# devices.net
KiCad netlist of a schematic drawn in Altium Designer
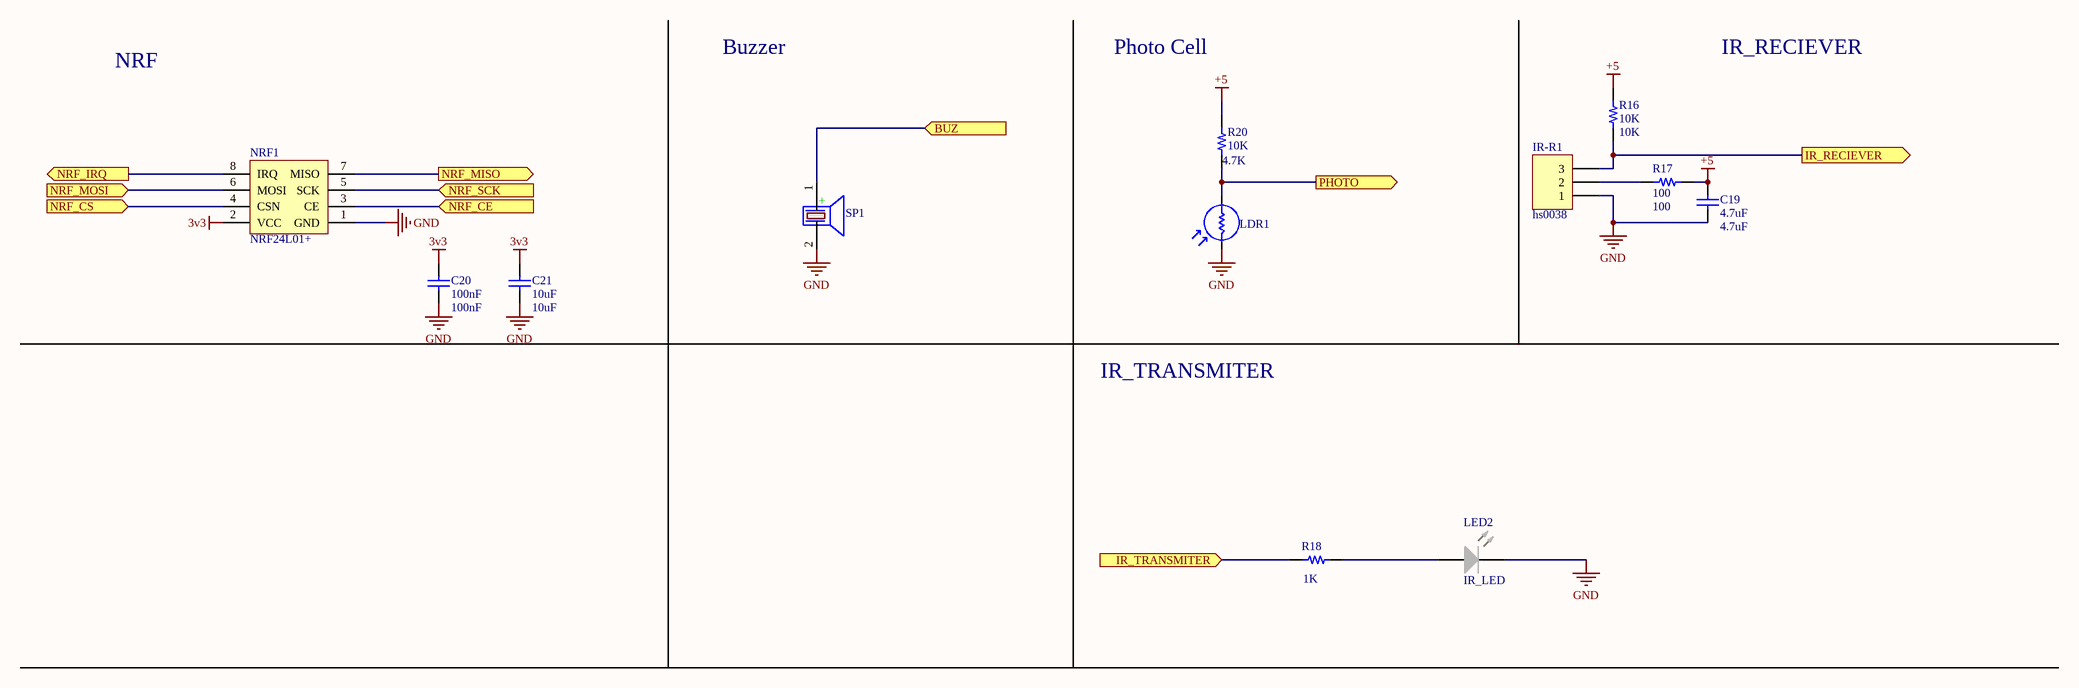
[diagram p0: devices.SchDoc]

(export (version "E")
  (design (tool "Eeschema 10.0.6"))
  (components
    (comp (ref "C19")
      (value "4.7uF")
      (footprint "0603C")
      (description "CAP SMD 0603")
      (fields (field (name "ALTIUM_VALUE") "4.7uF") (field (name "PUBLISHER") "Altium Limited"))
      (libsource (lib "Miscellaneous Devices") (part "Cap"))
    )
    (comp (ref "C20")
      (value "100nF")
      (footprint "0603C")
      (description "CAP SMD 0603")
      (fields (field (name "ALTIUM_VALUE") "100nF") (field (name "PUBLISHER") "Altium Limited"))
      (libsource (lib "Miscellaneous Devices") (part "Cap"))
    )
    (comp (ref "C21")
      (value "10uF")
      (footprint "0603C")
      (description "CAP SMD 0603")
      (fields (field (name "ALTIUM_VALUE") "10uF") (field (name "PUBLISHER") "Altium Limited"))
      (libsource (lib "Miscellaneous Devices") (part "Cap"))
    )
    (comp (ref "IR-R1")
      (value "hs0038")
      (footprint "HS3800B")
      (description "Header, 3-Pin, Right Angle")
      (fields (field (name "PUBLISHER") "Altium Limited"))
      (libsource (lib "Miscellaneous Connectors") (part "Header 3H"))
    )
    (comp (ref "LDR1")
      (value "PhotoCell-5mm")
      (footprint "PhotoCell")
      (description "Photo Cell- Variable Resistor With Light")
      (fields (field (name "DESIGNER") "Saeid Jorablo"))
      (libsource (lib "monitor_panel") (part "LDR"))
    )
    (comp (ref "LED2") (value "IR_LED") (footprint "LED_WHITE") (libsource (lib "LED5") (part "LED-W")))
    (comp (ref "NRF1")
      (value "NRF24L01+")
      (footprint "NRF24L01P")
      (description "NRF Module")
      (libsource (lib "monitor_panel") (part "NRF24L01P"))
    )
    (comp (ref "R16")
      (value "10K")
      (footprint "0603R")
      (description "RES SMD 0603")
      (fields (field (name "PART NUMBER") "RCS0805100KFKEA") (field (name "ALTIUM_VALUE") "10K"))
      (libsource (lib "lamp control-ver2") (part "Resistor"))
    )
    (comp (ref "R17")
      (value "100")
      (footprint "0603R")
      (description "RES SMD 0603")
      (fields (field (name "PART NUMBER") "RCS0805100KFKEA") (field (name "ALTIUM_VALUE") "100"))
      (libsource (lib "lamp control-ver2") (part "Resistor"))
    )
    (comp (ref "R18")
      (value "1K")
      (footprint "0603R")
      (description "RES SMD 0603")
      (fields (field (name "PART NUMBER") "RCS0805100KFKEA"))
      (libsource (lib "lamp control-ver2") (part "Resistor"))
    )
    (comp (ref "R20")
      (value "10K")
      (footprint "0603R")
      (description "RES SMD 0603")
      (fields (field (name "PART NUMBER") "RCS0805100KFKEA") (field (name "ALTIUM_VALUE") "4.7K"))
      (libsource (lib "lamp control-ver2") (part "Resistor"))
    )
    (comp (ref "SP1")
      (value "BUZZER")
      (footprint "BUZZER 7.62mm DC")
      (description "PIEZO BUZZER 5VOLTS")
      (fields (field (name "DESIGNER") "Abbas Basereh") (field (name "PUBLISHER") "Abbas Basereh"))
      (libsource (lib "monitor_panel") (part "PIEZO BUZZER"))
    )
  )
  (nets
    (net (code "1") (name "+5") (class "Default")
      (node (ref "C19") (pin "2") (pinfunction "2_2") (pintype "passive"))
      (node (ref "R16") (pin "1") (pinfunction "1_1") (pintype "passive"))
      (node (ref "R17") (pin "1") (pinfunction "1_1") (pintype "passive"))
      (node (ref "R20") (pin "1") (pinfunction "1_1") (pintype "passive"))
    )
    (net (code "2") (name "/BUZ") (class "Default")
      (node (ref "SP1") (pin "1") (pinfunction "+_1") (pintype "passive"))
    )
    (net (code "3") (name "/IR_RECIEVER") (class "Default")
      (node (ref "IR-R1") (pin "3") (pinfunction "3_3") (pintype "passive"))
      (node (ref "R16") (pin "2") (pinfunction "2_2") (pintype "passive"))
    )
    (net (code "4") (name "/IR_TRANSMITER") (class "Default")
      (node (ref "R18") (pin "2") (pinfunction "2_2") (pintype "passive"))
    )
    (net (code "5") (name "/NRF_CE") (class "Default")
      (node (ref "NRF1") (pin "3") (pinfunction "CE_3") (pintype "passive"))
    )
    (net (code "6") (name "/NRF_CS") (class "Default")
      (node (ref "NRF1") (pin "4") (pinfunction "CSN_4") (pintype "passive"))
    )
    (net (code "7") (name "/NRF_IRQ") (class "Default")
      (node (ref "NRF1") (pin "8") (pinfunction "IRQ_8") (pintype "passive"))
    )
    (net (code "8") (name "/NRF_MISO") (class "Default")
      (node (ref "NRF1") (pin "7") (pinfunction "MISO_7") (pintype "passive"))
    )
    (net (code "9") (name "/NRF_MOSI") (class "Default")
      (node (ref "NRF1") (pin "6") (pinfunction "MOSI_6") (pintype "passive"))
    )
    (net (code "10") (name "/NRF_SCK") (class "Default")
      (node (ref "NRF1") (pin "5") (pinfunction "SCK_5") (pintype "passive"))
    )
    (net (code "11") (name "/PHOTO") (class "Default")
      (node (ref "LDR1") (pin "2") (pintype "passive"))
      (node (ref "R20") (pin "2") (pinfunction "2_2") (pintype "passive"))
    )
    (net (code "12") (name "3v3") (class "Default")
      (node (ref "C20") (pin "2") (pinfunction "2_2") (pintype "passive"))
      (node (ref "C21") (pin "2") (pinfunction "2_2") (pintype "passive"))
      (node (ref "NRF1") (pin "2") (pinfunction "VCC_2") (pintype "passive"))
    )
    (net (code "13") (name "GND") (class "Default")
      (node (ref "C19") (pin "1") (pinfunction "1_1") (pintype "passive"))
      (node (ref "C20") (pin "1") (pinfunction "1_1") (pintype "passive"))
      (node (ref "C21") (pin "1") (pinfunction "1_1") (pintype "passive"))
      (node (ref "IR-R1") (pin "1") (pinfunction "1_1") (pintype "passive"))
      (node (ref "LDR1") (pin "1") (pintype "passive"))
      (node (ref "LED2") (pin "K") (pinfunction "K_K") (pintype "passive"))
      (node (ref "NRF1") (pin "1") (pinfunction "GND_1") (pintype "passive"))
      (node (ref "SP1") (pin "2") (pinfunction "-_2") (pintype "passive"))
    )
    (net (code "14") (name "Net-(IR-R1-Pad2)") (class "Default")
      (node (ref "IR-R1") (pin "2") (pinfunction "2_2") (pintype "passive"))
      (node (ref "R17") (pin "2") (pinfunction "2_2") (pintype "passive"))
    )
    (net (code "15") (name "Net-(LED2-PadA)") (class "Default")
      (node (ref "LED2") (pin "A") (pinfunction "A_A") (pintype "passive"))
      (node (ref "R18") (pin "1") (pinfunction "1_1") (pintype "passive"))
    )
  )
)
